# buggym.net
KiCad netlist of a schematic drawn in EAGLE
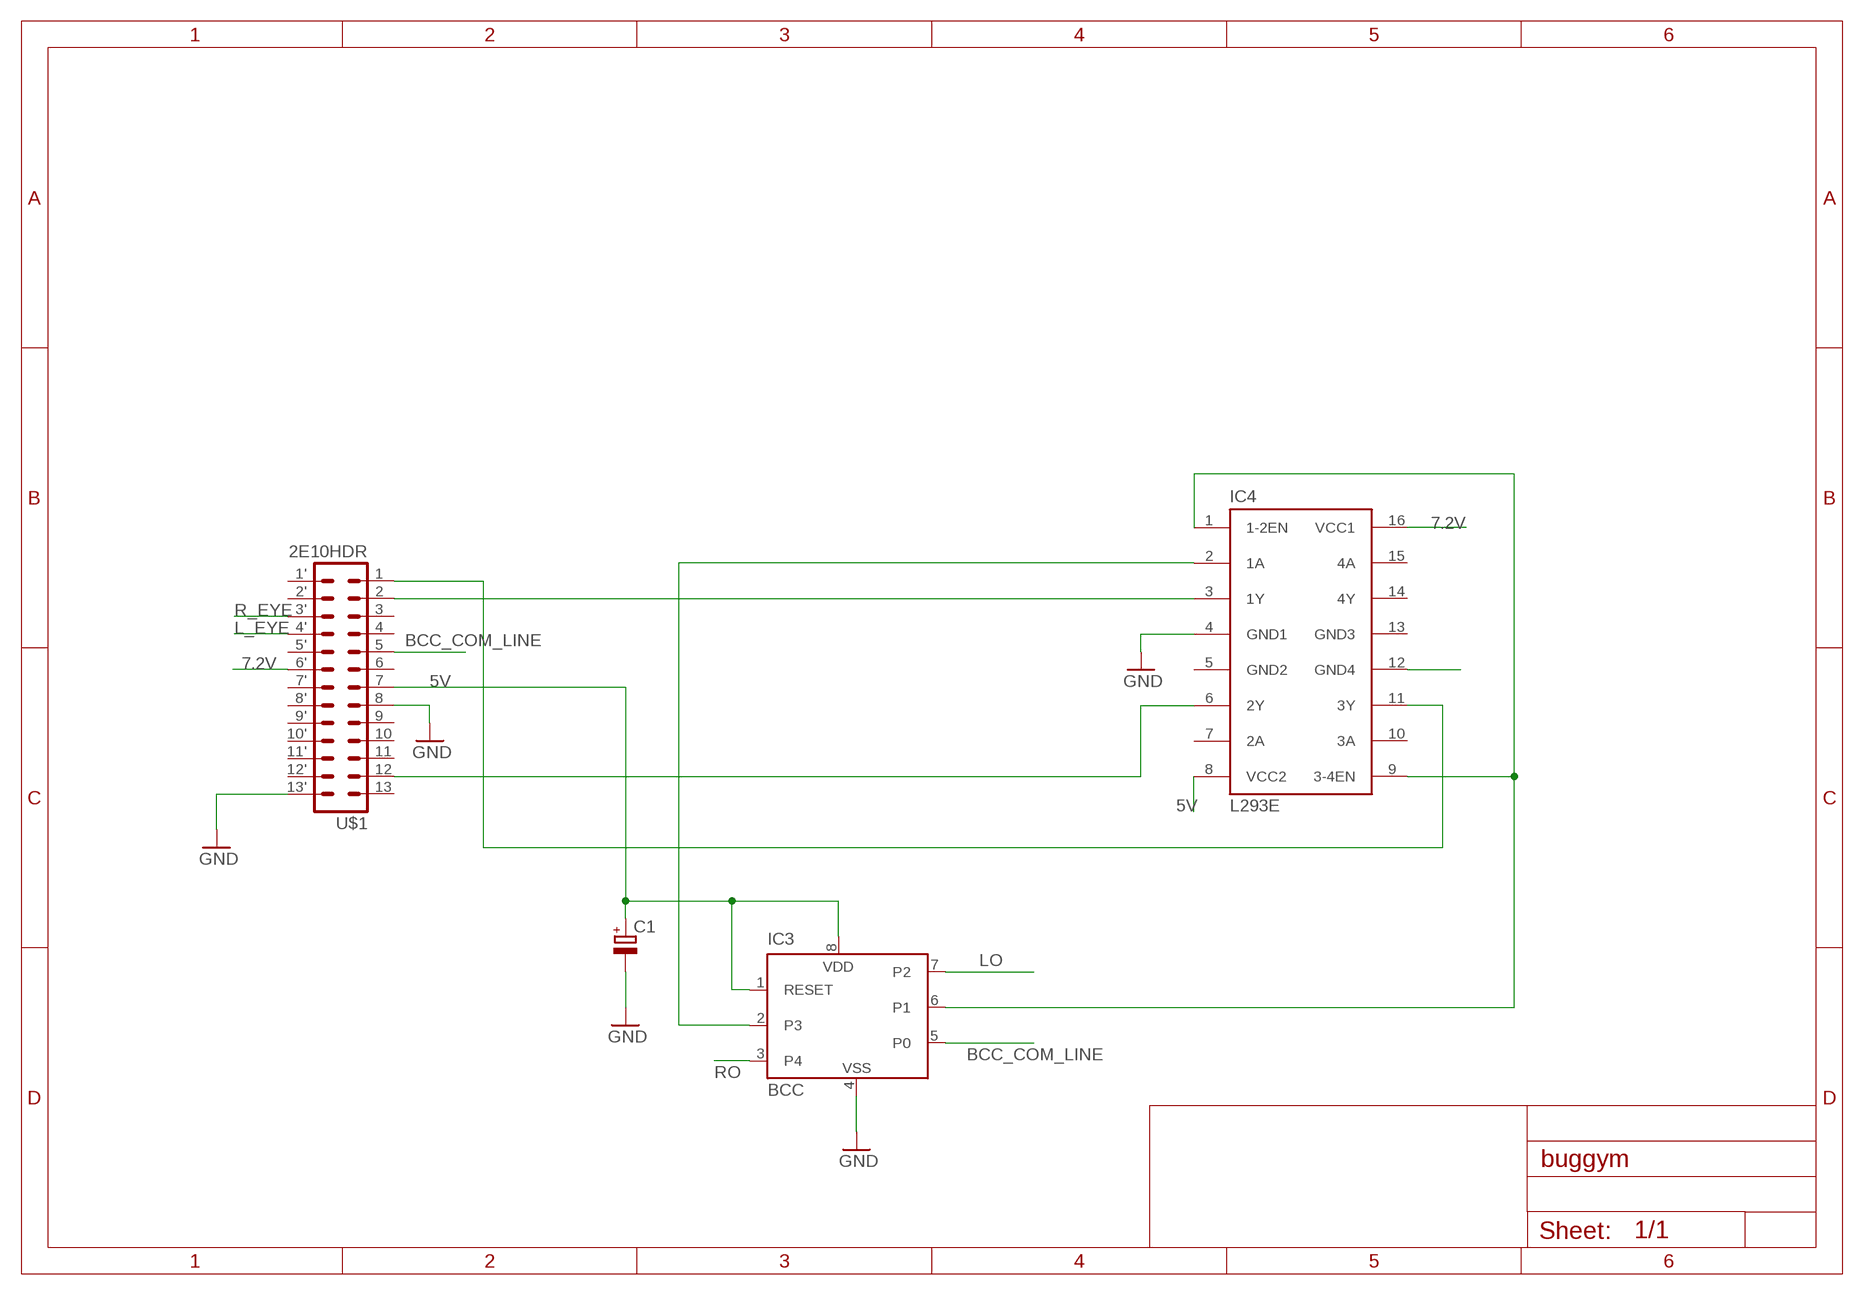
[diagram p0: schematic, sheet 1]

(export (version "E")
  (design (tool "Eeschema 10.0.6"))
  (components
    (comp (ref "C1")
      (value "CPOL-EUE5-4")
      (footprint "eagle-import:E5-4")
      (libsource (lib "eagle-import") (part "CPOL-EUE5-4"))
    )
    (comp (ref "IC3")
      (value "BCC")
      (footprint "eagle-import:DIL8")
      (libsource (lib "eagle-import") (part "BCC"))
    )
    (comp (ref "IC4")
      (value "L293E")
      (footprint "eagle-import:DIL16")
      (fields (field (name "MF") "Arrow Electronics"))
      (libsource (lib "eagle-import") (part "L293E"))
    )
    (comp (ref "U$1")
      (value "2E10HDR")
      (footprint "eagle-import:2E10BOARD")
      (libsource (lib "eagle-import") (part "2E10HDR"))
    )
  )
  (nets
    (net (code "1") (name "/5V") (class "Default")
      (node (ref "C1") (pin "+") (pinfunction "+_+") (pintype "passive"))
      (node (ref "IC3") (pin "1") (pinfunction "RESET_1") (pintype "bidirectional"))
      (node (ref "IC3") (pin "8") (pinfunction "5V_8") (pintype "power_in"))
      (node (ref "IC4") (pin "8") (pinfunction "VCC2_8") (pintype "power_in"))
      (node (ref "U$1") (pin "7") (pinfunction "7_7") (pintype "passive"))
    )
    (net (code "2") (name "/7.2V") (class "Default")
      (node (ref "IC4") (pin "16") (pinfunction "VCC1_16") (pintype "power_in"))
      (node (ref "U$1") (pin "6'") (pinfunction "6'_6'") (pintype "passive"))
    )
    (net (code "3") (name "/BCC_COM_LINE") (class "Default")
      (node (ref "IC3") (pin "5") (pinfunction "P0_5") (pintype "bidirectional"))
      (node (ref "U$1") (pin "5") (pinfunction "5_5") (pintype "passive"))
    )
    (net (code "4") (name "/GND2") (class "Default")
      (node (ref "IC4") (pin "5") (pinfunction "GND2_5") (pintype "power_in"))
    )
    (net (code "5") (name "/GND3") (class "Default")
      (node (ref "IC4") (pin "13") (pinfunction "GND3_13") (pintype "power_in"))
    )
    (net (code "6") (name "/LO") (class "Default")
      (node (ref "IC3") (pin "7") (pinfunction "P2_7") (pintype "bidirectional"))
    )
    (net (code "7") (name "/L_EYE") (class "Default")
      (node (ref "U$1") (pin "4'") (pinfunction "4'_4'") (pintype "passive"))
    )
    (net (code "8") (name "/RO") (class "Default")
      (node (ref "IC3") (pin "3") (pinfunction "P4_3") (pintype "input"))
    )
    (net (code "9") (name "/R_EYE") (class "Default")
      (node (ref "U$1") (pin "3'") (pinfunction "3'_3'") (pintype "passive"))
    )
    (net (code "10") (name "GND") (class "Default")
      (node (ref "C1") (pin "-") (pinfunction "-_-") (pintype "passive"))
      (node (ref "IC3") (pin "4") (pinfunction "VSS_4") (pintype "power_in"))
      (node (ref "IC4") (pin "4") (pinfunction "GND1_4") (pintype "power_in"))
      (node (ref "U$1") (pin "13'") (pinfunction "13'_13'") (pintype "passive"))
      (node (ref "U$1") (pin "8") (pinfunction "8_8") (pintype "passive"))
    )
    (net (code "11") (name "Net-(IC3-P1)") (class "Default")
      (node (ref "IC3") (pin "6") (pinfunction "P1_6") (pintype "bidirectional"))
      (node (ref "IC4") (pin "1") (pinfunction "1-2EN_1") (pintype "input"))
      (node (ref "IC4") (pin "9") (pinfunction "3-4EN_9") (pintype "input"))
    )
    (net (code "12") (name "Net-(IC3-P3)") (class "Default")
      (node (ref "IC3") (pin "2") (pinfunction "P3_2") (pintype "bidirectional"))
      (node (ref "IC4") (pin "2") (pinfunction "1A_2") (pintype "input"))
    )
    (net (code "13") (name "Net-(IC4-1Y)") (class "Default")
      (node (ref "IC4") (pin "3") (pinfunction "1Y_3") (pintype "output"))
      (node (ref "U$1") (pin "2") (pinfunction "2_2") (pintype "passive"))
    )
    (net (code "14") (name "Net-(IC4-2Y)") (class "Default")
      (node (ref "IC4") (pin "6") (pinfunction "2Y_6") (pintype "output"))
      (node (ref "U$1") (pin "12") (pinfunction "12_12") (pintype "passive"))
    )
    (net (code "15") (name "Net-(IC4-3Y)") (class "Default")
      (node (ref "IC4") (pin "11") (pinfunction "3Y_11") (pintype "output"))
      (node (ref "U$1") (pin "1") (pinfunction "1_1") (pintype "passive"))
    )
    (net (code "16") (name "unconnected-(IC4-2A-Pad7)") (class "Default")
      (node (ref "IC4") (pin "7") (pinfunction "2A_7") (pintype "input"))
    )
    (net (code "17") (name "unconnected-(IC4-3A-Pad10)") (class "Default")
      (node (ref "IC4") (pin "10") (pinfunction "3A_10") (pintype "input"))
    )
    (net (code "18") (name "unconnected-(IC4-4A-Pad15)") (class "Default")
      (node (ref "IC4") (pin "15") (pinfunction "4A_15") (pintype "input"))
    )
    (net (code "19") (name "unconnected-(IC4-4Y-Pad14)") (class "Default")
      (node (ref "IC4") (pin "14") (pinfunction "4Y_14") (pintype "output"))
    )
    (net (code "20") (name "unconnected-(IC4-GND4-Pad12)") (class "Default")
      (node (ref "IC4") (pin "12") (pinfunction "GND4_12") (pintype "power_in"))
    )
    (net (code "21") (name "unconnected-(U$1-Pad1')") (class "Default")
      (node (ref "U$1") (pin "1'") (pinfunction "1'_1'") (pintype "passive"))
    )
    (net (code "22") (name "unconnected-(U$1-Pad2')") (class "Default")
      (node (ref "U$1") (pin "2'") (pinfunction "2'_2'") (pintype "passive"))
    )
    (net (code "23") (name "unconnected-(U$1-Pad3)") (class "Default")
      (node (ref "U$1") (pin "3") (pinfunction "3_3") (pintype "passive"))
    )
    (net (code "24") (name "unconnected-(U$1-Pad4)") (class "Default")
      (node (ref "U$1") (pin "4") (pinfunction "4_4") (pintype "passive"))
    )
    (net (code "25") (name "unconnected-(U$1-Pad5')") (class "Default")
      (node (ref "U$1") (pin "5'") (pinfunction "5'_5'") (pintype "passive"))
    )
    (net (code "26") (name "unconnected-(U$1-Pad6)") (class "Default")
      (node (ref "U$1") (pin "6") (pinfunction "6_6") (pintype "passive"))
    )
    (net (code "27") (name "unconnected-(U$1-Pad7')") (class "Default")
      (node (ref "U$1") (pin "7'") (pinfunction "7'_7'") (pintype "passive"))
    )
    (net (code "28") (name "unconnected-(U$1-Pad8')") (class "Default")
      (node (ref "U$1") (pin "8'") (pinfunction "8'_8'") (pintype "passive"))
    )
    (net (code "29") (name "unconnected-(U$1-Pad9')") (class "Default")
      (node (ref "U$1") (pin "9'") (pinfunction "9'_9'") (pintype "passive"))
    )
    (net (code "30") (name "unconnected-(U$1-Pad9)") (class "Default")
      (node (ref "U$1") (pin "9") (pinfunction "9_9") (pintype "passive"))
    )
    (net (code "31") (name "unconnected-(U$1-Pad10')") (class "Default")
      (node (ref "U$1") (pin "10'") (pinfunction "10'_10'") (pintype "passive"))
    )
    (net (code "32") (name "unconnected-(U$1-Pad10)") (class "Default")
      (node (ref "U$1") (pin "10") (pinfunction "10_10") (pintype "passive"))
    )
    (net (code "33") (name "unconnected-(U$1-Pad11')") (class "Default")
      (node (ref "U$1") (pin "11'") (pinfunction "11'_11'") (pintype "passive"))
    )
    (net (code "34") (name "unconnected-(U$1-Pad11)") (class "Default")
      (node (ref "U$1") (pin "11") (pinfunction "11_11") (pintype "passive"))
    )
    (net (code "35") (name "unconnected-(U$1-Pad12')") (class "Default")
      (node (ref "U$1") (pin "12'") (pinfunction "12'_12'") (pintype "passive"))
    )
    (net (code "36") (name "unconnected-(U$1-Pad13)") (class "Default")
      (node (ref "U$1") (pin "13") (pinfunction "13_13") (pintype "passive"))
    )
  )
)
